# bioamplifier-00.net
KiCad netlist of a schematic drawn in EAGLE
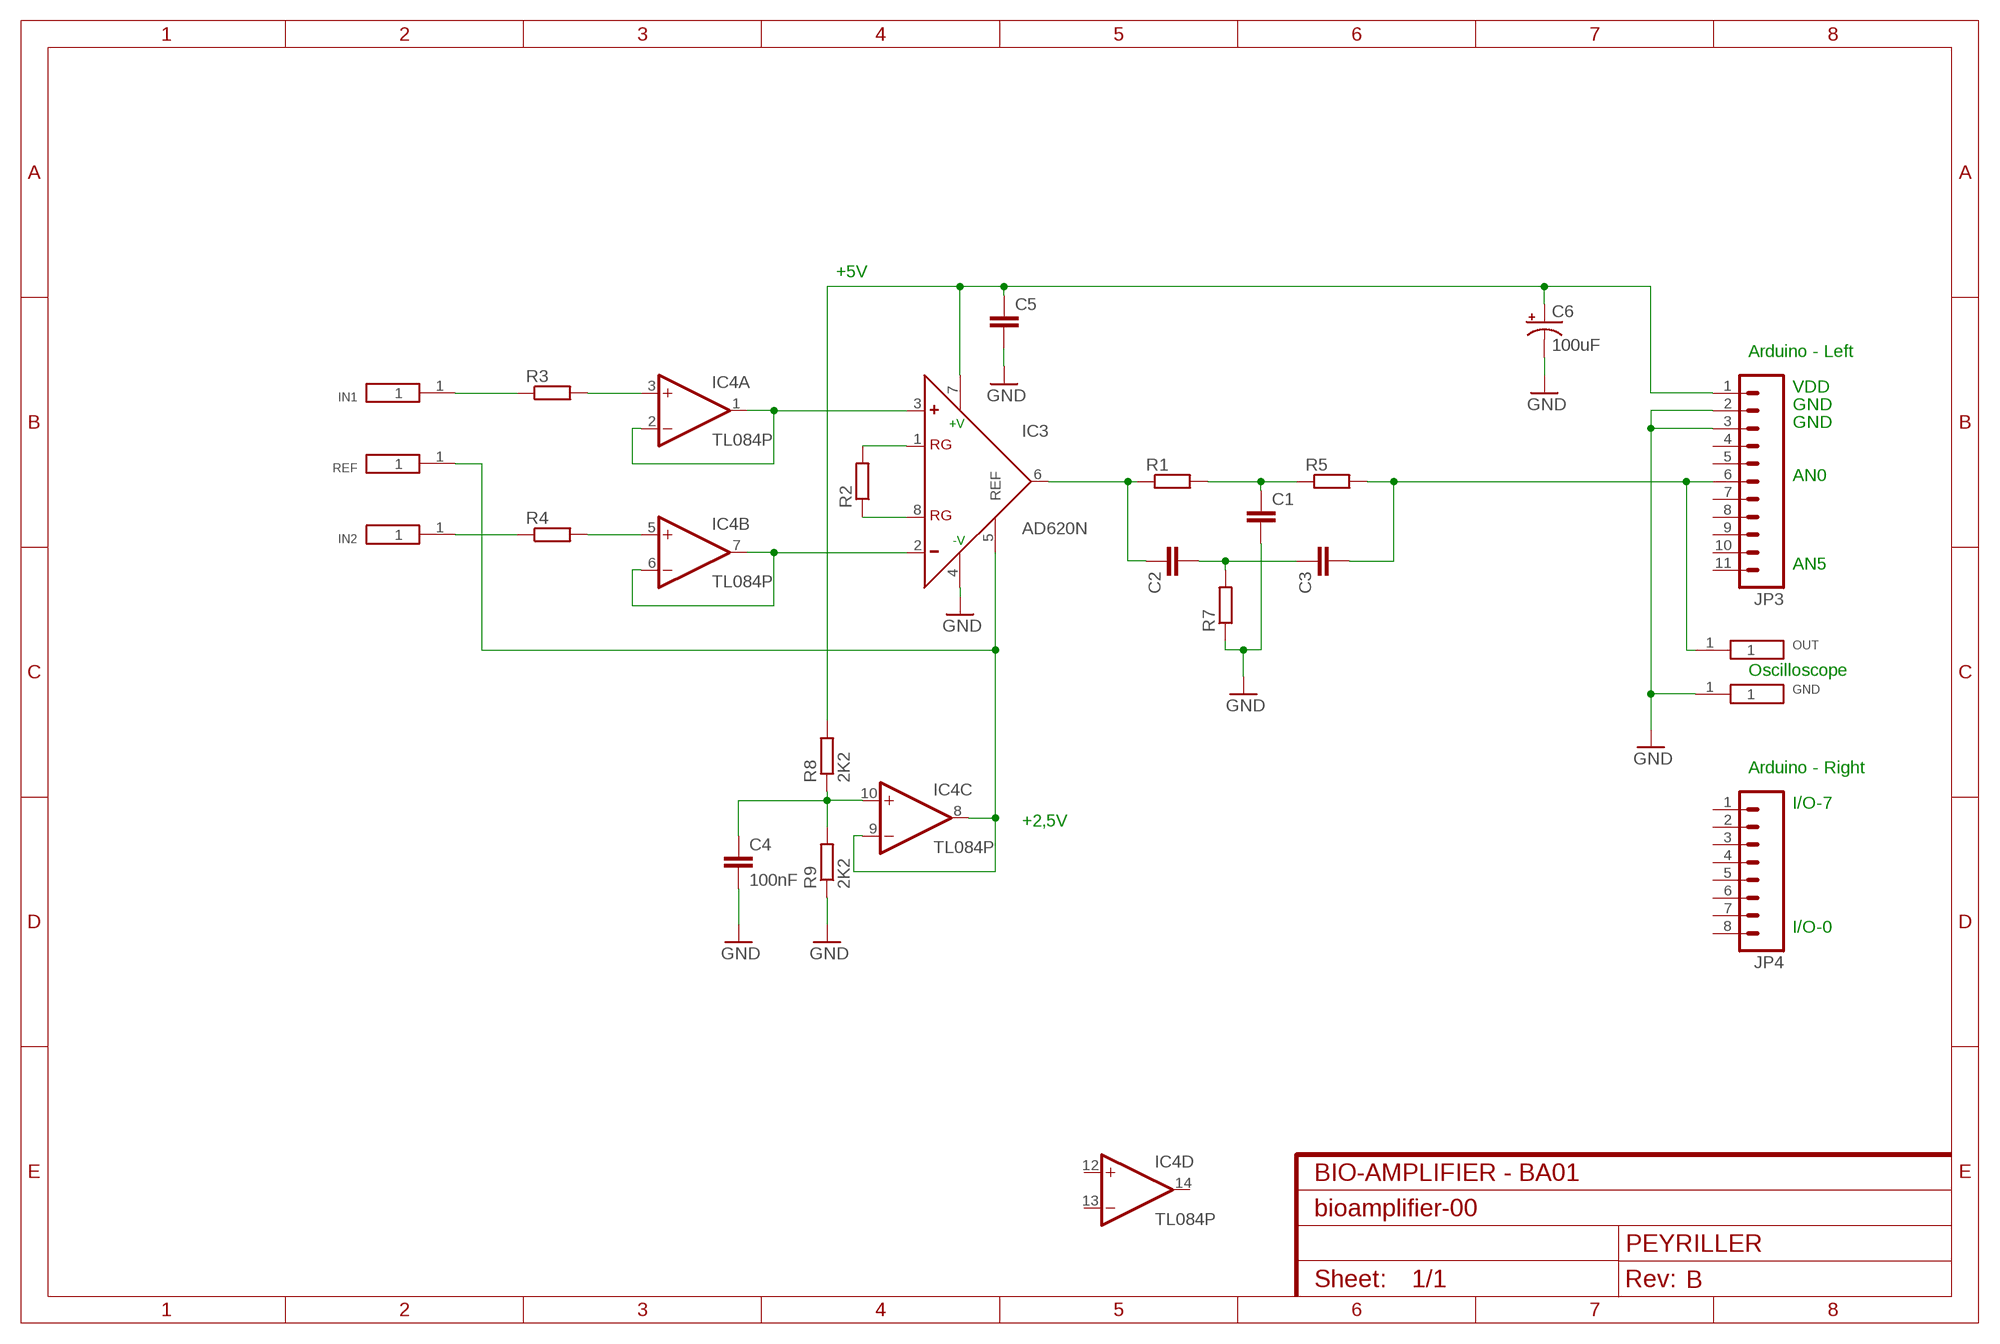
[diagram p0: schematic, sheet 1]

(export (version "E")
  (design (tool "Eeschema 10.0.6"))
  (components
    (comp (ref "C1")
      (value "C5/3")
      (footprint "eagle-import:C5B3")
      (libsource (lib "eagle-import") (part "C5/3"))
    )
    (comp (ref "C2")
      (value "C5/3")
      (footprint "eagle-import:C5B3")
      (libsource (lib "eagle-import") (part "C5/3"))
    )
    (comp (ref "C3")
      (value "C5/3")
      (footprint "eagle-import:C5B3")
      (libsource (lib "eagle-import") (part "C5/3"))
    )
    (comp (ref "C4")
      (value "100nF")
      (footprint "eagle-import:C5B3")
      (libsource (lib "eagle-import") (part "C5/3"))
    )
    (comp (ref "C5")
      (value "C5/3")
      (footprint "eagle-import:C5B3")
      (libsource (lib "eagle-import") (part "C5/3"))
    )
    (comp (ref "C6")
      (value "100uF")
      (footprint "eagle-import:EIA7343")
      (libsource (lib "eagle-import") (part "100UF-10V-10%(TANT)"))
    )
    (comp (ref "GND")
      (value "PAD1")
      (footprint "eagle-import:PAD1")
      (libsource (lib "eagle-import") (part "PAD1"))
    )
    (comp (ref "IC3")
      (value "AD620N")
      (footprint "eagle-import:DIL08")
      (fields (field (name "MF") "ALTERA CORPORATION") (field (name "MPN") "AD620AN"))
      (libsource (lib "eagle-import") (part "AD620N"))
    )
    (comp (ref "IC4")
      (value "TL084P")
      (footprint "eagle-import:DIL14")
      (libsource (lib "eagle-import") (part "TL084P"))
    )
    (comp (ref "IN1")
      (value "PAD1")
      (footprint "eagle-import:PAD1")
      (libsource (lib "eagle-import") (part "PAD1"))
    )
    (comp (ref "IN2")
      (value "PAD1")
      (footprint "eagle-import:PAD1")
      (libsource (lib "eagle-import") (part "PAD1"))
    )
    (comp (ref "JP3")
      (value "M11LONGPADS")
      (footprint "eagle-import:1X11_LONGPADS")
      (libsource (lib "eagle-import") (part "M11LONGPADS"))
    )
    (comp (ref "JP4")
      (value "M08LONGPADS")
      (footprint "eagle-import:1X08_LONGPADS")
      (libsource (lib "eagle-import") (part "M08LONGPADS"))
    )
    (comp (ref "OUT")
      (value "PAD1")
      (footprint "eagle-import:PAD1")
      (libsource (lib "eagle-import") (part "PAD1"))
    )
    (comp (ref "R1")
      (value "R-EU_0207/10")
      (footprint "eagle-import:0207_10")
      (libsource (lib "eagle-import") (part "R-EU_0207/10"))
    )
    (comp (ref "R2")
      (value "R-EU_0207/10")
      (footprint "eagle-import:0207_10")
      (libsource (lib "eagle-import") (part "R-EU_0207/10"))
    )
    (comp (ref "R3")
      (value "R-EU_0207/10")
      (footprint "eagle-import:0207_10")
      (libsource (lib "eagle-import") (part "R-EU_0207/10"))
    )
    (comp (ref "R4")
      (value "R-EU_0207/10")
      (footprint "eagle-import:0207_10")
      (libsource (lib "eagle-import") (part "R-EU_0207/10"))
    )
    (comp (ref "R5")
      (value "R-EU_0207/10")
      (footprint "eagle-import:0207_10")
      (libsource (lib "eagle-import") (part "R-EU_0207/10"))
    )
    (comp (ref "R7")
      (value "R-EU_0207/10")
      (footprint "eagle-import:0207_10")
      (libsource (lib "eagle-import") (part "R-EU_0207/10"))
    )
    (comp (ref "R8")
      (value "2K2")
      (footprint "eagle-import:0207_10")
      (libsource (lib "eagle-import") (part "R-EU_0207/10"))
    )
    (comp (ref "R9")
      (value "2K2")
      (footprint "eagle-import:0207_10")
      (libsource (lib "eagle-import") (part "R-EU_0207/10"))
    )
    (comp (ref "REF")
      (value "PAD1")
      (footprint "eagle-import:PAD1")
      (libsource (lib "eagle-import") (part "PAD1"))
    )
  )
  (nets
    (net (code "1") (name "GND") (class "Default")
      (node (ref "C1") (pin "2") (pinfunction "2_2") (pintype "passive"))
      (node (ref "C4") (pin "2") (pinfunction "2_2") (pintype "passive"))
      (node (ref "C5") (pin "2") (pinfunction "2_2") (pintype "passive"))
      (node (ref "C6") (pin "C") (pinfunction "-_C") (pintype "passive"))
      (node (ref "GND") (pin "1") (pinfunction "1_1") (pintype "bidirectional"))
      (node (ref "IC3") (pin "4") (pinfunction "-V_4") (pintype "power_in"))
      (node (ref "JP3") (pin "2") (pinfunction "2_2") (pintype "passive"))
      (node (ref "JP3") (pin "3") (pinfunction "3_3") (pintype "passive"))
      (node (ref "R7") (pin "1") (pinfunction "1_1") (pintype "passive"))
      (node (ref "R9") (pin "1") (pinfunction "1_1") (pintype "passive"))
    )
    (net (code "2") (name "Net-(C1-Pad1)") (class "Default")
      (node (ref "C1") (pin "1") (pinfunction "1_1") (pintype "passive"))
      (node (ref "R1") (pin "2") (pinfunction "2_2") (pintype "passive"))
      (node (ref "R5") (pin "1") (pinfunction "1_1") (pintype "passive"))
    )
    (net (code "3") (name "Net-(C2-Pad2)") (class "Default")
      (node (ref "C2") (pin "2") (pinfunction "2_2") (pintype "passive"))
      (node (ref "C3") (pin "1") (pinfunction "1_1") (pintype "passive"))
      (node (ref "R7") (pin "2") (pinfunction "2_2") (pintype "passive"))
    )
    (net (code "4") (name "Net-(C3-Pad2)") (class "Default")
      (node (ref "C3") (pin "2") (pinfunction "2_2") (pintype "passive"))
      (node (ref "JP3") (pin "6") (pinfunction "6_6") (pintype "passive"))
      (node (ref "OUT") (pin "1") (pinfunction "1_1") (pintype "bidirectional"))
      (node (ref "R5") (pin "2") (pinfunction "2_2") (pintype "passive"))
    )
    (net (code "5") (name "Net-(C6-+)") (class "Default")
      (node (ref "C5") (pin "1") (pinfunction "1_1") (pintype "passive"))
      (node (ref "C6") (pin "A") (pinfunction "+_A") (pintype "passive"))
      (node (ref "IC3") (pin "7") (pinfunction "+V_7") (pintype "power_in"))
      (node (ref "JP3") (pin "1") (pinfunction "1_1") (pintype "passive"))
      (node (ref "R8") (pin "2") (pinfunction "2_2") (pintype "passive"))
    )
    (net (code "6") (name "Net-(IC3-+)") (class "Default")
      (node (ref "IC3") (pin "3") (pinfunction "+_3") (pintype "input"))
      (node (ref "IC4") (pin "1") (pinfunction "OUT_1") (pintype "output"))
      (node (ref "IC4") (pin "2") (pinfunction "-IN_2") (pintype "input"))
    )
    (net (code "7") (name "Net-(IC3--)") (class "Default")
      (node (ref "IC3") (pin "2") (pinfunction "-_2") (pintype "input"))
      (node (ref "IC4") (pin "6") (pinfunction "-IN_6") (pintype "input"))
      (node (ref "IC4") (pin "7") (pinfunction "OUT_7") (pintype "output"))
    )
    (net (code "8") (name "Net-(IC3-OUT)") (class "Default")
      (node (ref "C2") (pin "1") (pinfunction "1_1") (pintype "passive"))
      (node (ref "IC3") (pin "6") (pinfunction "OUT_6") (pintype "output"))
      (node (ref "R1") (pin "1") (pinfunction "1_1") (pintype "passive"))
    )
    (net (code "9") (name "Net-(IC3-REF)") (class "Default")
      (node (ref "IC3") (pin "5") (pinfunction "REF_5") (pintype "passive"))
      (node (ref "IC4") (pin "8") (pinfunction "OUT_8") (pintype "output"))
      (node (ref "IC4") (pin "9") (pinfunction "-IN_9") (pintype "input"))
      (node (ref "REF") (pin "1") (pinfunction "1_1") (pintype "bidirectional"))
    )
    (net (code "10") (name "Net-(IC3-RG-Pad1)") (class "Default")
      (node (ref "IC3") (pin "1") (pinfunction "RG_1") (pintype "passive"))
      (node (ref "R2") (pin "2") (pinfunction "2_2") (pintype "passive"))
    )
    (net (code "11") (name "Net-(IC3-RG-Pad8)") (class "Default")
      (node (ref "IC3") (pin "8") (pinfunction "RG_8") (pintype "passive"))
      (node (ref "R2") (pin "1") (pinfunction "1_1") (pintype "passive"))
    )
    (net (code "12") (name "Net-(IC4A-+IN)") (class "Default")
      (node (ref "IC4") (pin "3") (pinfunction "+IN_3") (pintype "input"))
      (node (ref "R3") (pin "2") (pinfunction "2_2") (pintype "passive"))
    )
    (net (code "13") (name "Net-(IC4B-+IN)") (class "Default")
      (node (ref "IC4") (pin "5") (pinfunction "+IN_5") (pintype "input"))
      (node (ref "R4") (pin "2") (pinfunction "2_2") (pintype "passive"))
    )
    (net (code "14") (name "Net-(IC4C-+IN)") (class "Default")
      (node (ref "C4") (pin "1") (pinfunction "1_1") (pintype "passive"))
      (node (ref "IC4") (pin "10") (pinfunction "+IN_10") (pintype "input"))
      (node (ref "R8") (pin "1") (pinfunction "1_1") (pintype "passive"))
      (node (ref "R9") (pin "2") (pinfunction "2_2") (pintype "passive"))
    )
    (net (code "15") (name "Net-(IN1-Pad1)") (class "Default")
      (node (ref "IN1") (pin "1") (pinfunction "1_1") (pintype "bidirectional"))
      (node (ref "R3") (pin "1") (pinfunction "1_1") (pintype "passive"))
    )
    (net (code "16") (name "Net-(IN2-Pad1)") (class "Default")
      (node (ref "IN2") (pin "1") (pinfunction "1_1") (pintype "bidirectional"))
      (node (ref "R4") (pin "1") (pinfunction "1_1") (pintype "passive"))
    )
    (net (code "17") (name "unconnected-(IC4D-+IN-Pad12)") (class "Default")
      (node (ref "IC4") (pin "12") (pinfunction "+IN_12") (pintype "input"))
    )
    (net (code "18") (name "unconnected-(IC4D--IN-Pad13)") (class "Default")
      (node (ref "IC4") (pin "13") (pinfunction "-IN_13") (pintype "input"))
    )
    (net (code "19") (name "unconnected-(IC4D-OUT-Pad14)") (class "Default")
      (node (ref "IC4") (pin "14") (pinfunction "OUT_14") (pintype "output"))
    )
    (net (code "20") (name "unconnected-(JP3-Pad4)") (class "Default")
      (node (ref "JP3") (pin "4") (pinfunction "4_4") (pintype "passive"))
    )
    (net (code "21") (name "unconnected-(JP3-Pad5)") (class "Default")
      (node (ref "JP3") (pin "5") (pinfunction "5_5") (pintype "passive"))
    )
    (net (code "22") (name "unconnected-(JP3-Pad7)") (class "Default")
      (node (ref "JP3") (pin "7") (pinfunction "7_7") (pintype "passive"))
    )
    (net (code "23") (name "unconnected-(JP3-Pad8)") (class "Default")
      (node (ref "JP3") (pin "8") (pinfunction "8_8") (pintype "passive"))
    )
    (net (code "24") (name "unconnected-(JP3-Pad9)") (class "Default")
      (node (ref "JP3") (pin "9") (pinfunction "9_9") (pintype "passive"))
    )
    (net (code "25") (name "unconnected-(JP3-Pad10)") (class "Default")
      (node (ref "JP3") (pin "10") (pinfunction "10_10") (pintype "passive"))
    )
    (net (code "26") (name "unconnected-(JP3-Pad11)") (class "Default")
      (node (ref "JP3") (pin "11") (pinfunction "11_11") (pintype "passive"))
    )
    (net (code "27") (name "unconnected-(JP4-Pad1)") (class "Default")
      (node (ref "JP4") (pin "1") (pinfunction "1_1") (pintype "passive"))
    )
    (net (code "28") (name "unconnected-(JP4-Pad2)") (class "Default")
      (node (ref "JP4") (pin "2") (pinfunction "2_2") (pintype "passive"))
    )
    (net (code "29") (name "unconnected-(JP4-Pad3)") (class "Default")
      (node (ref "JP4") (pin "3") (pinfunction "3_3") (pintype "passive"))
    )
    (net (code "30") (name "unconnected-(JP4-Pad4)") (class "Default")
      (node (ref "JP4") (pin "4") (pinfunction "4_4") (pintype "passive"))
    )
    (net (code "31") (name "unconnected-(JP4-Pad5)") (class "Default")
      (node (ref "JP4") (pin "5") (pinfunction "5_5") (pintype "passive"))
    )
    (net (code "32") (name "unconnected-(JP4-Pad6)") (class "Default")
      (node (ref "JP4") (pin "6") (pinfunction "6_6") (pintype "passive"))
    )
    (net (code "33") (name "unconnected-(JP4-Pad7)") (class "Default")
      (node (ref "JP4") (pin "7") (pinfunction "7_7") (pintype "passive"))
    )
    (net (code "34") (name "unconnected-(JP4-Pad8)") (class "Default")
      (node (ref "JP4") (pin "8") (pinfunction "8_8") (pintype "passive"))
    )
  )
)
